# TAKEMINAKATA.net
KiCad netlist of a schematic drawn in EasyEDA
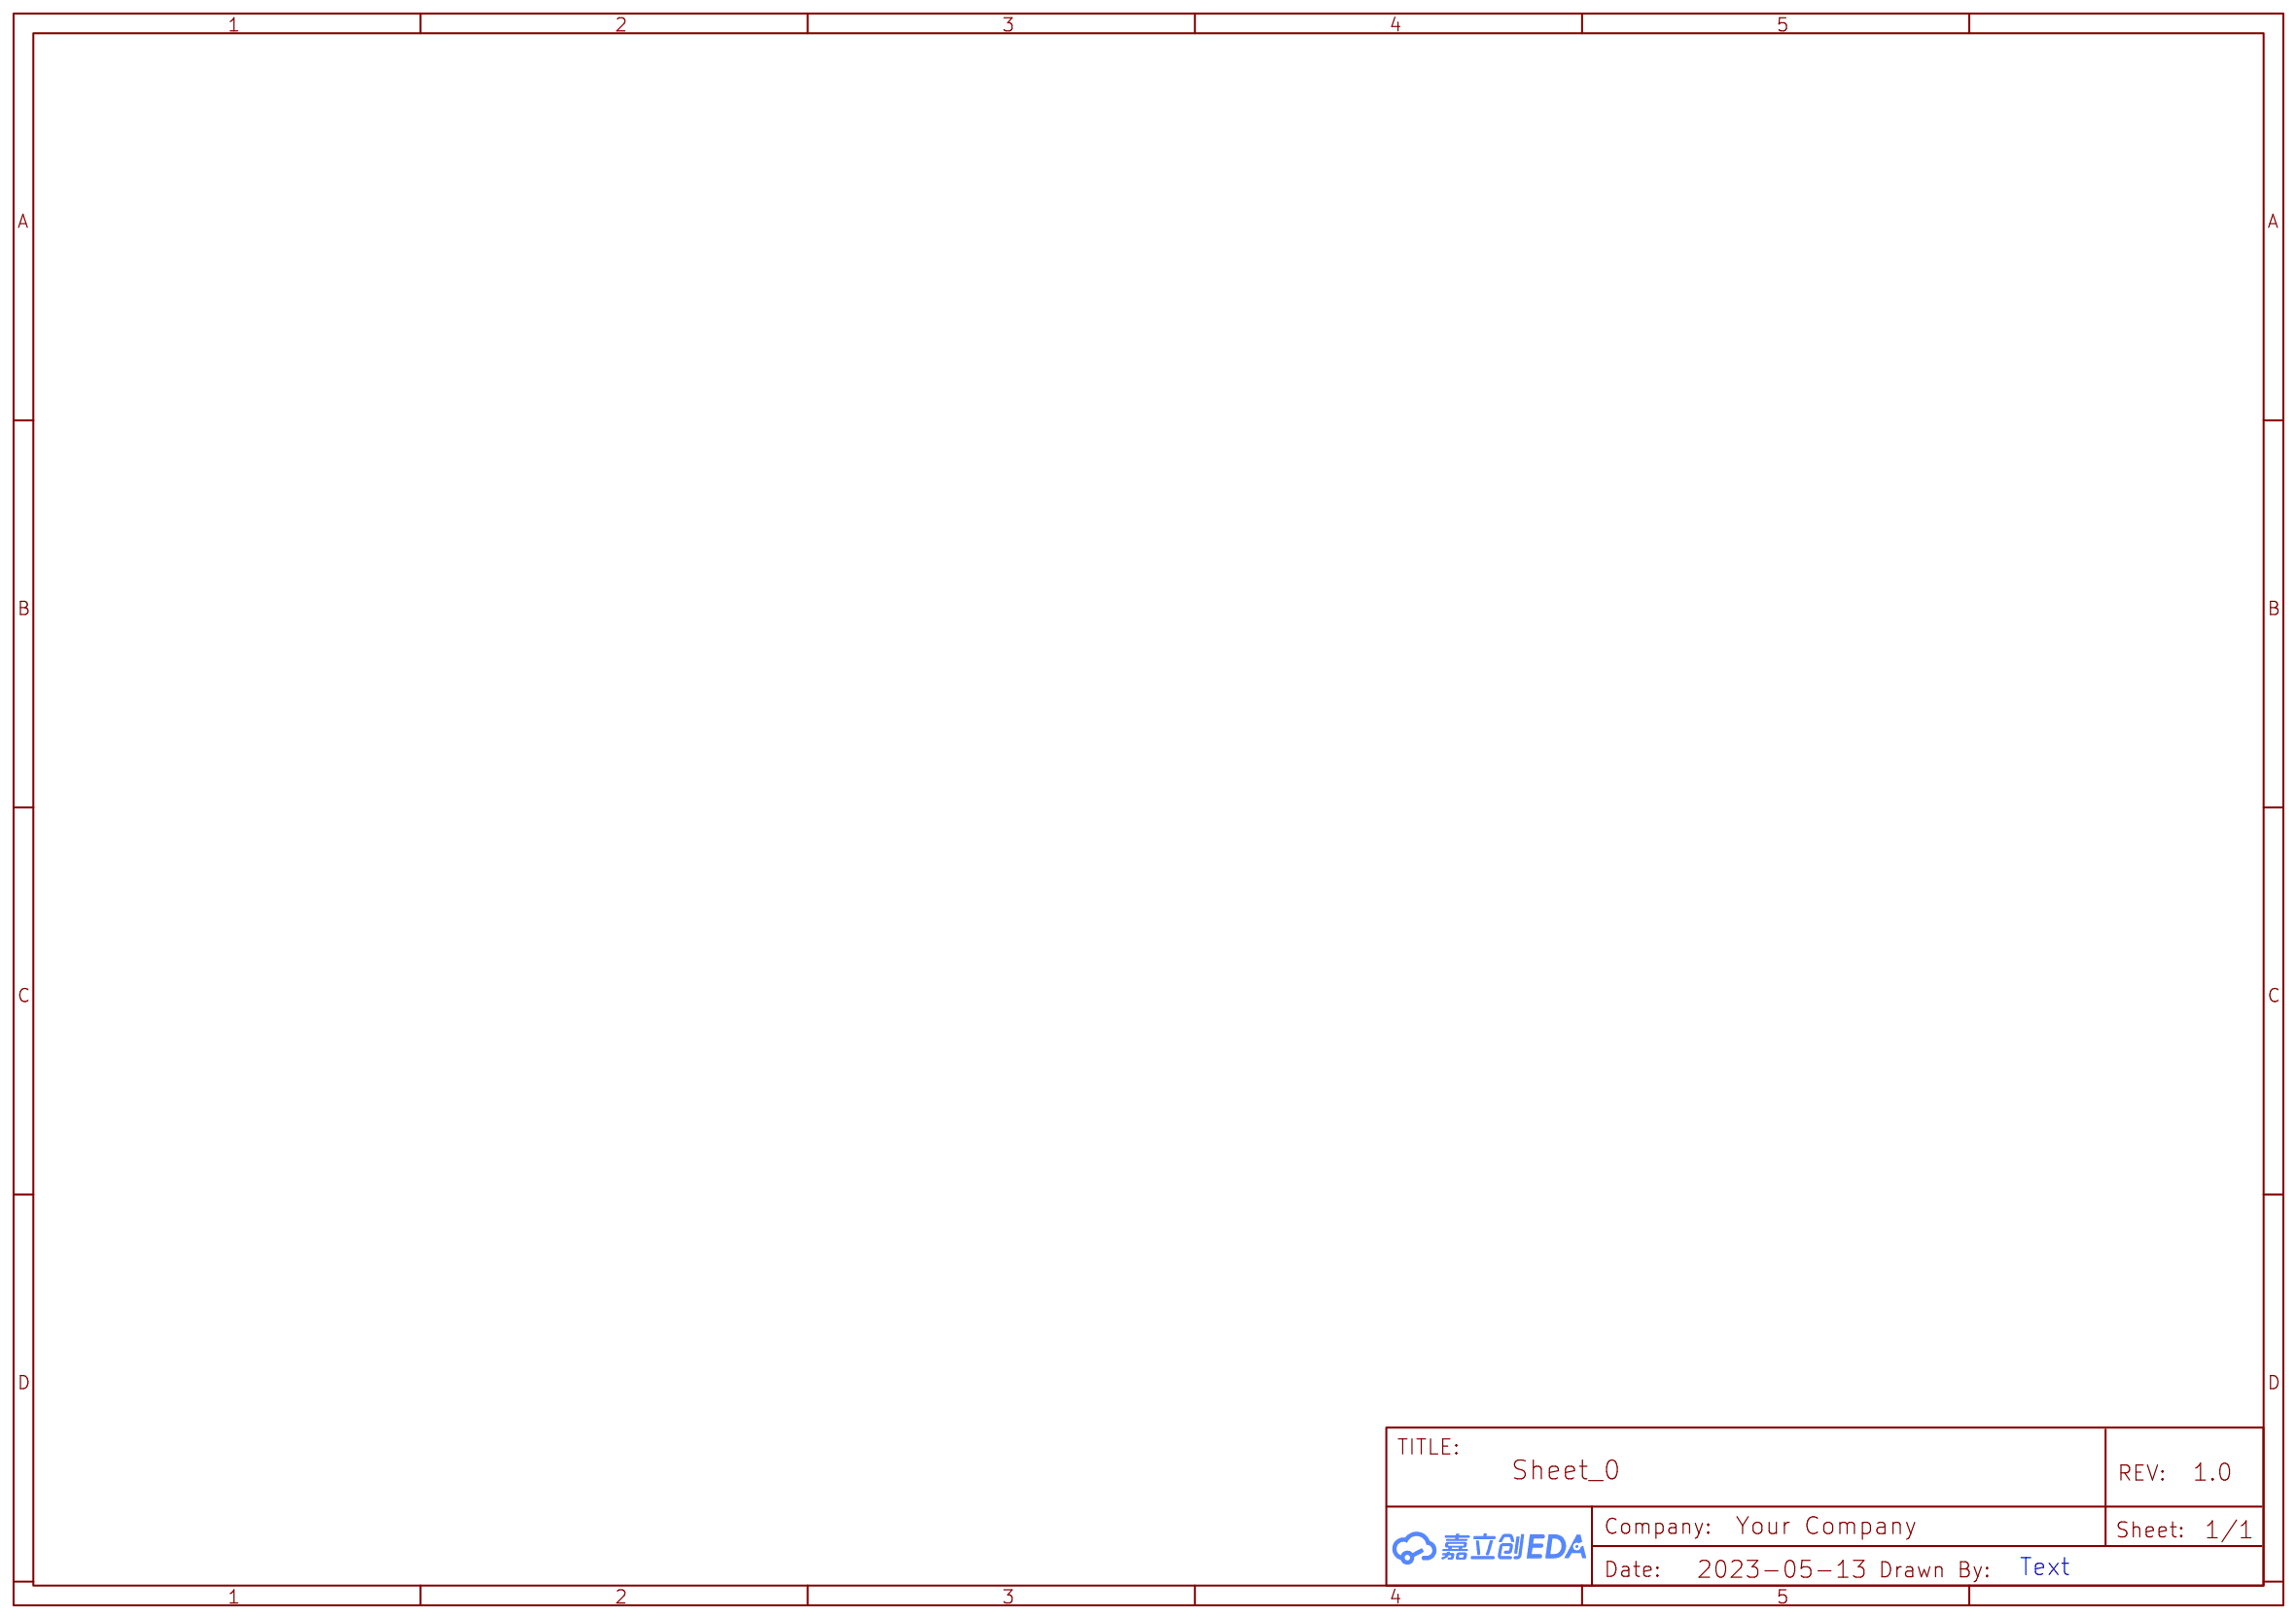
[diagram p0: Sheet_1]
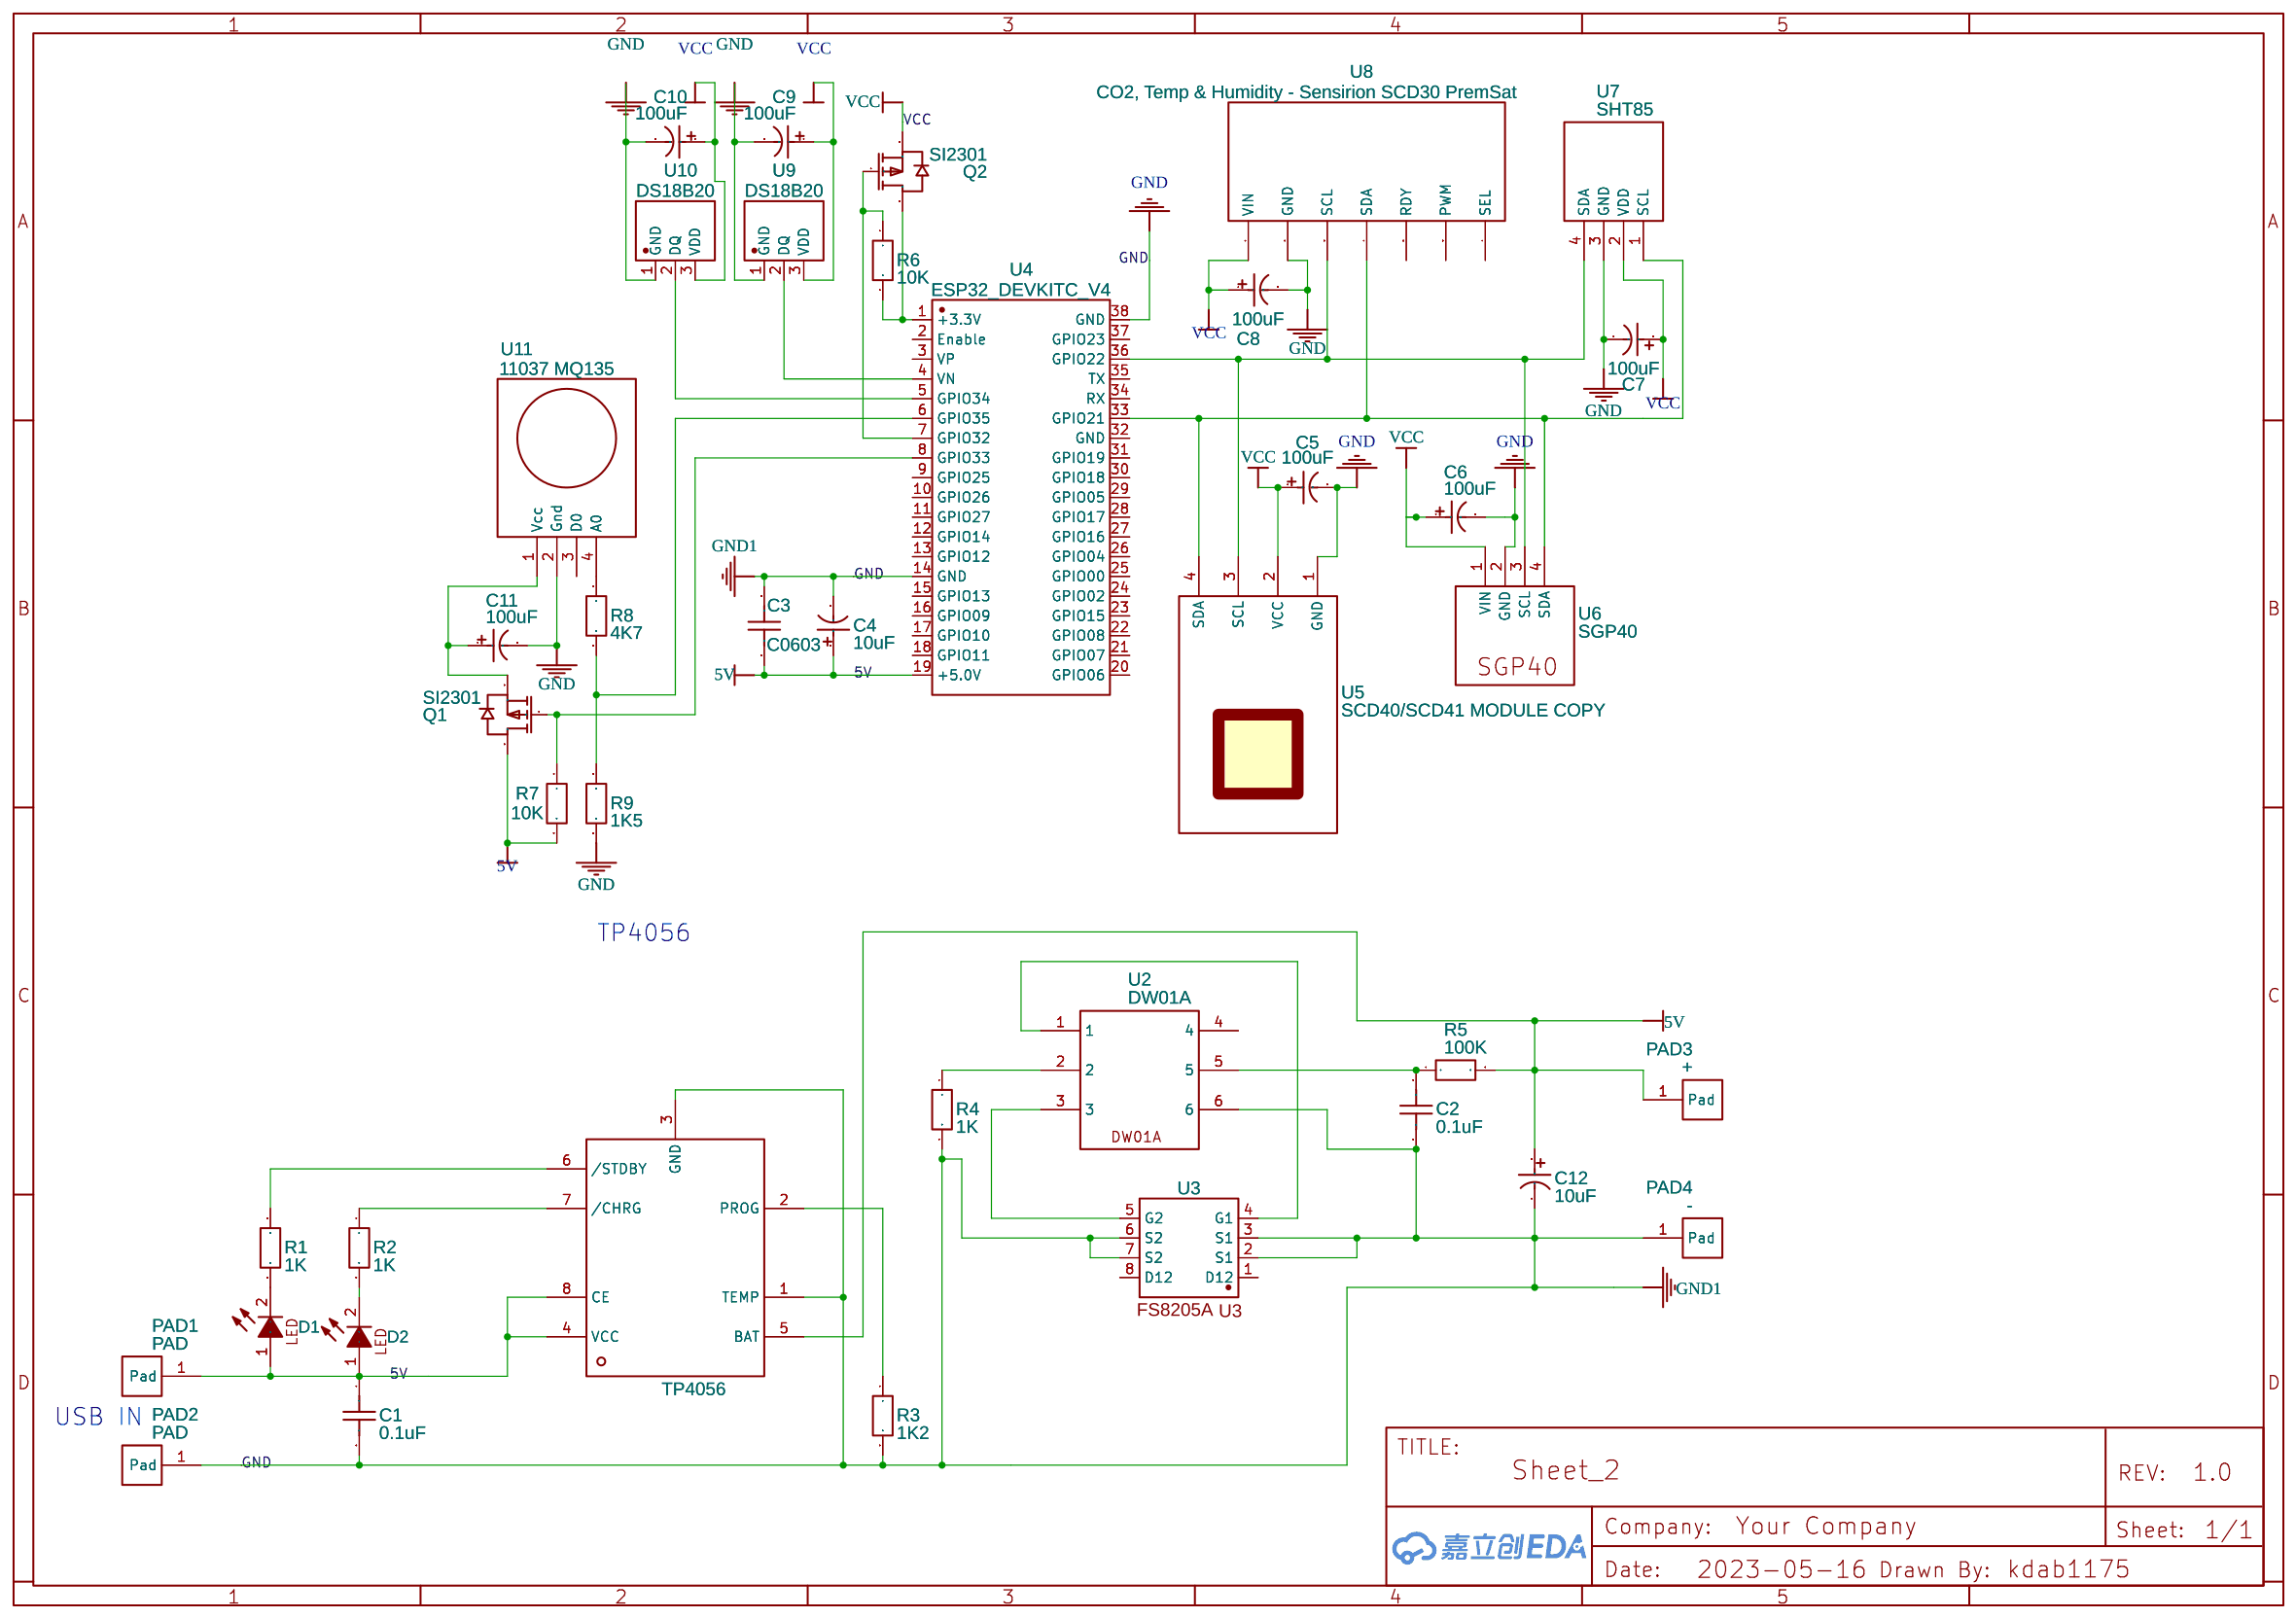
[diagram p1: Sheet_2]

(export (version "E")
  (design (tool "Eeschema 10.0.6"))
  (components
    (comp (ref "C1") (value "0.1uF") (libsource (lib "") (part "C_0603_US")))
    (comp (ref "C2") (value "0.1uF") (libsource (lib "") (part "C_0603_US")))
    (comp (ref "C3")
      (value "C0603")
      (fields (field (name "BOM_Manufacturer Part") "10uF") (field (name "BOM_Supplier Part") "C15415"))
      (libsource (lib "") (part "C 0603"))
    )
    (comp (ref "C4")
      (value "10uF")
      (fields
        (field (name "BOM_Manufacturer Part") "KF106M016B05RR0VH2FP0")
        (field (name "BOM_Supplier Part") "C43798")
      )
      (libsource (lib "") (part "10uF 16V 3*5_1"))
    )
    (comp (ref "C5")
      (value "100uF")
      (fields
        (field (name "BOM_Manufacturer Part") "100uF 35V 6.3*11")
        (field (name "BOM_Supplier Part") "C45076")
      )
      (libsource (lib "") (part "100uF 35V 6.3*11_C45076_1"))
    )
    (comp (ref "C6")
      (value "100uF")
      (fields
        (field (name "BOM_Manufacturer Part") "100uF 35V 6.3*11")
        (field (name "BOM_Supplier Part") "C45076")
      )
      (libsource (lib "") (part "100uF 35V 6.3*11_C45076_1"))
    )
    (comp (ref "C7")
      (value "100uF")
      (fields
        (field (name "BOM_Manufacturer Part") "100uF 35V 6.3*11")
        (field (name "BOM_Supplier Part") "C45076")
      )
      (libsource (lib "") (part "100uF 35V 6.3*11_C45076_2"))
    )
    (comp (ref "C8")
      (value "100uF")
      (fields
        (field (name "BOM_Manufacturer Part") "100uF 35V 6.3*11")
        (field (name "BOM_Supplier Part") "C45076")
      )
      (libsource (lib "") (part "100uF 35V 6.3*11_C45076_1"))
    )
    (comp (ref "C9")
      (value "100uF")
      (fields
        (field (name "BOM_Manufacturer Part") "100uF 35V 6.3*11")
        (field (name "BOM_Supplier Part") "C45076")
      )
      (libsource (lib "") (part "100uF 35V 6.3*11_C45076"))
    )
    (comp (ref "C10")
      (value "100uF")
      (fields
        (field (name "BOM_Manufacturer Part") "100uF 35V 6.3*11")
        (field (name "BOM_Supplier Part") "C45076")
      )
      (libsource (lib "") (part "100uF 35V 6.3*11_C45076"))
    )
    (comp (ref "C11")
      (value "100uF")
      (fields
        (field (name "BOM_Manufacturer Part") "100uF 35V 6.3*11")
        (field (name "BOM_Supplier Part") "C45076")
      )
      (libsource (lib "") (part "100uF 35V 6.3*11_C45076_1"))
    )
    (comp (ref "C12")
      (value "10uF")
      (fields
        (field (name "BOM_Manufacturer Part") "KF106M016B05RR0VH2FP0")
        (field (name "BOM_Supplier Part") "C43798")
      )
      (libsource (lib "") (part "10uF 16V 3*5"))
    )
    (comp (ref "D1")
      (value "LED")
      (fields (field (name "BOM_Manufacturer Part") "5600") (field (name "BOM_Supplier Part") "L20325-ND"))
      (libsource (lib "") (part "LED"))
    )
    (comp (ref "D2")
      (value "LED COPY")
      (fields (field (name "BOM_Manufacturer Part") "5600") (field (name "BOM_Supplier Part") "L20325-ND"))
      (libsource (lib "") (part "LED"))
    )
    (comp (ref "PAD1") (value "PAD") (libsource (lib "") (part "PAD COPY COPY_1")))
    (comp (ref "PAD2") (value "PAD") (libsource (lib "") (part "PAD COPY COPY_1")))
    (comp (ref "PAD3") (value "+") (libsource (lib "") (part "PAD COPY COPY")))
    (comp (ref "PAD4") (value "-") (libsource (lib "") (part "PAD COPY COPY")))
    (comp (ref "Q1")
      (value "SI2301")
      (fields (field (name "BOM_Manufacturer Part") "SI2301DS") (field (name "BOM_Supplier Part") "C2841444"))
      (libsource (lib "") (part "SI2301DS_TH"))
    )
    (comp (ref "Q2")
      (value "SI2301")
      (fields (field (name "BOM_Manufacturer Part") "SI2301DS") (field (name "BOM_Supplier Part") "C2841444"))
      (libsource (lib "") (part "SI2301DS_TH_1"))
    )
    (comp (ref "R1") (value "1K") (libsource (lib "") (part "R_0603_EU_1")))
    (comp (ref "R2") (value "1K") (libsource (lib "") (part "R_0603_EU_1")))
    (comp (ref "R3") (value "1K2") (libsource (lib "") (part "R_0603_EU_1")))
    (comp (ref "R4") (value "1K") (libsource (lib "") (part "R_0603_EU_1")))
    (comp (ref "R5") (value "100K") (libsource (lib "") (part "R_0603_EU")))
    (comp (ref "R6") (value "10K") (libsource (lib "") (part "R_0603_EU_1")))
    (comp (ref "R7") (value "10K") (libsource (lib "") (part "R_0603_EU_1")))
    (comp (ref "R8") (value "4K7") (libsource (lib "") (part "R_0603_EU_1")))
    (comp (ref "R9") (value "1K5") (libsource (lib "") (part "R_0603_EU_1")))
    (comp (ref "U1")
      (value "TP4056")
      (fields
        (field (name "BOM_Manufacturer Part") "TP4056-42-SOP8-PP")
        (field (name "BOM_Supplier Part") "3656")
      )
      (libsource (lib "") (part "TP4056"))
    )
    (comp (ref "U2") (value "DW01A") (libsource (lib "") (part "DW01A")))
    (comp (ref "U3") (value "FS8205A MODIF") (libsource (lib "") (part "FS8205A MODIF")))
    (comp (ref "U4")
      (value "ESP32_DEVKITC_V4")
      (fields (field (name "BOM_Supplier Part") "A5130"))
      (libsource (lib "") (part "ESP32_DEVKITC_V4"))
    )
    (comp (ref "U5") (value "SCD40/SCD41 MODULE COPY") (libsource (lib "") (part "SCD40/SCD41 MODULE COPY")))
    (comp (ref "U6") (value "SGP40") (libsource (lib "") (part "SGP40")))
    (comp (ref "U7")
      (value "SHT85")
      (fields (field (name "BOM_Supplier Part") "403-SHT85"))
      (libsource (lib "") (part "SHT85"))
    )
    (comp (ref "U8")
      (value "CO2, Temp & Humidity - Sensirion SCD30 PremSat")
      (fields
        (field (name "BOM_Manufacturer Part") "SCD30")
        (field (name "BOM_Supplier Part") "1649-1098-ND")
      )
      (libsource (lib "") (part "CO2, Temp & Humidity - Sensirion SCD30 PremSat"))
    )
    (comp (ref "U9")
      (value "DS18B20")
      (fields (field (name "BOM_Supplier Part") "C5379069"))
      (libsource (lib "") (part "DS18B20_C5379069"))
    )
    (comp (ref "U10")
      (value "DS18B20")
      (fields (field (name "BOM_Supplier Part") "C5379069"))
      (libsource (lib "") (part "DS18B20_C5379069"))
    )
    (comp (ref "U11") (value "11037 MQ135") (libsource (lib "") (part "11037 MQ135")))
  )
  (nets
    (net (code "1") (name "5V") (class "Default")
      (node (ref "C1") (pin "1") (pinfunction "1_1") (pintype "unspecified"))
      (node (ref "C12") (pin "1") (pinfunction "1_1") (pintype "input"))
      (node (ref "C3") (pin "1") (pinfunction "1_1") (pintype "unspecified"))
      (node (ref "C4") (pin "1") (pinfunction "1_1") (pintype "input"))
      (node (ref "D1") (pin "1") (pinfunction "A_1") (pintype "unspecified"))
      (node (ref "D2") (pin "1") (pinfunction "A_1") (pintype "unspecified"))
      (node (ref "PAD1") (pin "1") (pinfunction "Pad_1") (pintype "unspecified"))
      (node (ref "PAD3") (pin "1") (pinfunction "Pad_1") (pintype "unspecified"))
      (node (ref "Q1") (pin "3") (pinfunction "D_3") (pintype "unspecified"))
      (node (ref "R5") (pin "2") (pinfunction "2_2") (pintype "unspecified"))
      (node (ref "R7") (pin "2") (pinfunction "2_2") (pintype "unspecified"))
      (node (ref "U1") (pin "4") (pinfunction "VCC_4") (pintype "unspecified"))
      (node (ref "U1") (pin "5") (pinfunction "BAT_5") (pintype "unspecified"))
      (node (ref "U1") (pin "8") (pinfunction "CE_8") (pintype "unspecified"))
      (node (ref "U4") (pin "19") (pinfunction "+5.0V_19") (pintype "unspecified"))
    )
    (net (code "2") (name "GND") (class "Default")
      (node (ref "C1") (pin "2") (pinfunction "2_2") (pintype "unspecified"))
      (node (ref "C10") (pin "2") (pinfunction "2_2") (pintype "input"))
      (node (ref "C11") (pin "2") (pinfunction "2_2") (pintype "input"))
      (node (ref "C12") (pin "2") (pinfunction "2_2") (pintype "input"))
      (node (ref "C2") (pin "2") (pinfunction "2_2") (pintype "unspecified"))
      (node (ref "C3") (pin "2") (pinfunction "2_2") (pintype "unspecified"))
      (node (ref "C4") (pin "2") (pinfunction "2_2") (pintype "input"))
      (node (ref "C5") (pin "2") (pinfunction "2_2") (pintype "input"))
      (node (ref "C6") (pin "2") (pinfunction "2_2") (pintype "input"))
      (node (ref "C7") (pin "2") (pinfunction "2_2") (pintype "input"))
      (node (ref "C8") (pin "2") (pinfunction "2_2") (pintype "input"))
      (node (ref "C9") (pin "2") (pinfunction "2_2") (pintype "input"))
      (node (ref "PAD2") (pin "1") (pinfunction "Pad_1") (pintype "unspecified"))
      (node (ref "PAD4") (pin "1") (pinfunction "Pad_1") (pintype "unspecified"))
      (node (ref "R3") (pin "2") (pinfunction "2_2") (pintype "unspecified"))
      (node (ref "R4") (pin "2") (pinfunction "2_2") (pintype "unspecified"))
      (node (ref "R9") (pin "2") (pinfunction "2_2") (pintype "unspecified"))
      (node (ref "U1") (pin "1") (pinfunction "TEMP_1") (pintype "unspecified"))
      (node (ref "U1") (pin "3") (pinfunction "GND_3") (pintype "unspecified"))
      (node (ref "U10") (pin "1") (pinfunction "GND_1") (pintype "unspecified"))
      (node (ref "U11") (pin "2") (pinfunction "Gnd_2") (pintype "unspecified"))
      (node (ref "U2") (pin "6") (pinfunction "6_6") (pintype "unspecified"))
      (node (ref "U3") (pin "2") (pinfunction "S1_2") (pintype "unspecified"))
      (node (ref "U3") (pin "3") (pinfunction "S1_3") (pintype "unspecified"))
      (node (ref "U3") (pin "6") (pinfunction "S2_6") (pintype "unspecified"))
      (node (ref "U3") (pin "7") (pinfunction "S2_7") (pintype "unspecified"))
      (node (ref "U4") (pin "14") (pinfunction "GND_14") (pintype "unspecified"))
      (node (ref "U4") (pin "38") (pinfunction "GND_38") (pintype "unspecified"))
      (node (ref "U5") (pin "1") (pinfunction "GND_1") (pintype "unspecified"))
      (node (ref "U6") (pin "2") (pinfunction "GND_2") (pintype "unspecified"))
      (node (ref "U7") (pin "3") (pinfunction "GND_3") (pintype "unspecified"))
      (node (ref "U8") (pin "2") (pinfunction "GND_2") (pintype "unspecified"))
      (node (ref "U9") (pin "1") (pinfunction "GND_1") (pintype "unspecified"))
    )
    (net (code "3") (name "Net-(C2-Pad1)") (class "Default")
      (node (ref "C2") (pin "1") (pinfunction "1_1") (pintype "unspecified"))
      (node (ref "R5") (pin "1") (pinfunction "1_1") (pintype "unspecified"))
      (node (ref "U2") (pin "5") (pinfunction "5_5") (pintype "unspecified"))
    )
    (net (code "4") (name "Net-(D1-K)") (class "Default")
      (node (ref "D1") (pin "2") (pinfunction "K_2") (pintype "unspecified"))
      (node (ref "R1") (pin "2") (pinfunction "2_2") (pintype "unspecified"))
    )
    (net (code "5") (name "Net-(D2-K)") (class "Default")
      (node (ref "D2") (pin "2") (pinfunction "K_2") (pintype "unspecified"))
      (node (ref "R2") (pin "2") (pinfunction "2_2") (pintype "unspecified"))
    )
    (net (code "6") (name "Net-(Q1-G)") (class "Default")
      (node (ref "Q1") (pin "1") (pinfunction "G_1") (pintype "unspecified"))
      (node (ref "R7") (pin "1") (pinfunction "1_1") (pintype "unspecified"))
      (node (ref "U4") (pin "8") (pinfunction "GPIO33_8") (pintype "unspecified"))
    )
    (net (code "7") (name "Net-(Q1-S)") (class "Default")
      (node (ref "C11") (pin "1") (pinfunction "1_1") (pintype "input"))
      (node (ref "Q1") (pin "2") (pinfunction "S_2") (pintype "unspecified"))
      (node (ref "U11") (pin "1") (pinfunction "Vcc_1") (pintype "unspecified"))
    )
    (net (code "8") (name "Net-(Q2-D)") (class "Default")
      (node (ref "Q2") (pin "3") (pinfunction "D_3") (pintype "unspecified"))
      (node (ref "R6") (pin "2") (pinfunction "2_2") (pintype "unspecified"))
      (node (ref "U4") (pin "1") (pinfunction "+3.3V_1") (pintype "unspecified"))
    )
    (net (code "9") (name "Net-(Q2-G)") (class "Default")
      (node (ref "Q2") (pin "1") (pinfunction "G_1") (pintype "unspecified"))
      (node (ref "R6") (pin "1") (pinfunction "1_1") (pintype "unspecified"))
      (node (ref "U4") (pin "7") (pinfunction "GPIO32_7") (pintype "unspecified"))
    )
    (net (code "10") (name "Net-(R4-Pad1)") (class "Default")
      (node (ref "R4") (pin "1") (pinfunction "1_1") (pintype "unspecified"))
      (node (ref "U2") (pin "2") (pinfunction "2_2") (pintype "unspecified"))
    )
    (net (code "11") (name "Net-(U1-PROG)") (class "Default")
      (node (ref "R3") (pin "1") (pinfunction "1_1") (pintype "unspecified"))
      (node (ref "U1") (pin "2") (pinfunction "PROG_2") (pintype "unspecified"))
    )
    (net (code "12") (name "Net-(U1-{slash}CHRG)") (class "Default")
      (node (ref "R2") (pin "1") (pinfunction "1_1") (pintype "unspecified"))
      (node (ref "U1") (pin "7") (pinfunction "/CHRG_7") (pintype "unspecified"))
    )
    (net (code "13") (name "Net-(U1-{slash}STDBY)") (class "Default")
      (node (ref "R1") (pin "1") (pinfunction "1_1") (pintype "unspecified"))
      (node (ref "U1") (pin "6") (pinfunction "/STDBY_6") (pintype "unspecified"))
    )
    (net (code "14") (name "Net-(U3-G1)") (class "Default")
      (node (ref "U2") (pin "1") (pinfunction "1_1") (pintype "unspecified"))
      (node (ref "U3") (pin "4") (pinfunction "G1_4") (pintype "unspecified"))
    )
    (net (code "15") (name "Net-(U3-G2)") (class "Default")
      (node (ref "U2") (pin "3") (pinfunction "3_3") (pintype "unspecified"))
      (node (ref "U3") (pin "5") (pinfunction "G2_5") (pintype "unspecified"))
    )
    (net (code "16") (name "Net-(U4-GPIO21)") (class "Default")
      (node (ref "U4") (pin "33") (pinfunction "GPIO21_33") (pintype "unspecified"))
      (node (ref "U5") (pin "4") (pinfunction "SDA_4") (pintype "unspecified"))
      (node (ref "U6") (pin "4") (pinfunction "SDA_4") (pintype "unspecified"))
      (node (ref "U7") (pin "1") (pinfunction "SCL_1") (pintype "unspecified"))
      (node (ref "U8") (pin "4") (pinfunction "SDA_4") (pintype "unspecified"))
    )
    (net (code "17") (name "Net-(U4-GPIO22)") (class "Default")
      (node (ref "U4") (pin "36") (pinfunction "GPIO22_36") (pintype "unspecified"))
      (node (ref "U5") (pin "3") (pinfunction "SCL_3") (pintype "unspecified"))
      (node (ref "U6") (pin "3") (pinfunction "SCL_3") (pintype "unspecified"))
      (node (ref "U7") (pin "4") (pinfunction "SDA_4") (pintype "unspecified"))
      (node (ref "U8") (pin "3") (pinfunction "SCL_3") (pintype "unspecified"))
    )
    (net (code "18") (name "Net-(U4-GPIO35)") (class "Default")
      (node (ref "R8") (pin "2") (pinfunction "2_2") (pintype "unspecified"))
      (node (ref "R9") (pin "1") (pinfunction "1_1") (pintype "unspecified"))
      (node (ref "U4") (pin "6") (pinfunction "GPIO35_6") (pintype "unspecified"))
    )
    (net (code "19") (name "Net-(U4-VN)") (class "Default")
      (node (ref "U4") (pin "4") (pinfunction "VN_4") (pintype "unspecified"))
      (node (ref "U9") (pin "2") (pinfunction "DQ_2") (pintype "unspecified"))
    )
    (net (code "20") (name "Net-(U10-DQ)") (class "Default")
      (node (ref "U10") (pin "2") (pinfunction "DQ_2") (pintype "unspecified"))
      (node (ref "U4") (pin "5") (pinfunction "GPIO34_5") (pintype "unspecified"))
    )
    (net (code "21") (name "Net-(U11-A0)") (class "Default")
      (node (ref "R8") (pin "1") (pinfunction "1_1") (pintype "unspecified"))
      (node (ref "U11") (pin "4") (pinfunction "A0_4") (pintype "unspecified"))
    )
    (net (code "22") (name "VCC") (class "Default")
      (node (ref "C10") (pin "1") (pinfunction "1_1") (pintype "input"))
      (node (ref "C5") (pin "1") (pinfunction "1_1") (pintype "input"))
      (node (ref "C6") (pin "1") (pinfunction "1_1") (pintype "input"))
      (node (ref "C7") (pin "1") (pinfunction "1_1") (pintype "input"))
      (node (ref "C8") (pin "1") (pinfunction "1_1") (pintype "input"))
      (node (ref "C9") (pin "1") (pinfunction "1_1") (pintype "input"))
      (node (ref "Q2") (pin "2") (pinfunction "S_2") (pintype "unspecified"))
      (node (ref "U10") (pin "3") (pinfunction "VDD_3") (pintype "unspecified"))
      (node (ref "U5") (pin "2") (pinfunction "VCC_2") (pintype "unspecified"))
      (node (ref "U6") (pin "1") (pinfunction "VIN_1") (pintype "unspecified"))
      (node (ref "U7") (pin "2") (pinfunction "VDD_2") (pintype "unspecified"))
      (node (ref "U8") (pin "1") (pinfunction "VIN_1") (pintype "unspecified"))
      (node (ref "U9") (pin "3") (pinfunction "VDD_3") (pintype "unspecified"))
    )
    (net (code "23") (name "unconnected-(U2-Pad4)") (class "Default")
      (node (ref "U2") (pin "4") (pinfunction "4_4") (pintype "unspecified"))
    )
    (net (code "24") (name "unconnected-(U3-D12-Pad1)") (class "Default")
      (node (ref "U3") (pin "1") (pinfunction "D12_1") (pintype "unspecified"))
    )
    (net (code "25") (name "unconnected-(U3-D12-Pad8)") (class "Default")
      (node (ref "U3") (pin "8") (pinfunction "D12_8") (pintype "unspecified"))
    )
    (net (code "26") (name "unconnected-(U4-Enable-Pad2)") (class "Default")
      (node (ref "U4") (pin "2") (pinfunction "Enable_2") (pintype "unspecified"))
    )
    (net (code "27") (name "unconnected-(U4-GND-Pad32)") (class "Default")
      (node (ref "U4") (pin "32") (pinfunction "GND_32") (pintype "unspecified"))
    )
    (net (code "28") (name "unconnected-(U4-GPIO00-Pad25)") (class "Default")
      (node (ref "U4") (pin "25") (pinfunction "GPIO00_25") (pintype "unspecified"))
    )
    (net (code "29") (name "unconnected-(U4-GPIO02-Pad24)") (class "Default")
      (node (ref "U4") (pin "24") (pinfunction "GPIO02_24") (pintype "unspecified"))
    )
    (net (code "30") (name "unconnected-(U4-GPIO04-Pad26)") (class "Default")
      (node (ref "U4") (pin "26") (pinfunction "GPIO04_26") (pintype "unspecified"))
    )
    (net (code "31") (name "unconnected-(U4-GPIO05-Pad29)") (class "Default")
      (node (ref "U4") (pin "29") (pinfunction "GPIO05_29") (pintype "unspecified"))
    )
    (net (code "32") (name "unconnected-(U4-GPIO06-Pad20)") (class "Default")
      (node (ref "U4") (pin "20") (pinfunction "GPIO06_20") (pintype "unspecified"))
    )
    (net (code "33") (name "unconnected-(U4-GPIO07-Pad21)") (class "Default")
      (node (ref "U4") (pin "21") (pinfunction "GPIO07_21") (pintype "unspecified"))
    )
    (net (code "34") (name "unconnected-(U4-GPIO08-Pad22)") (class "Default")
      (node (ref "U4") (pin "22") (pinfunction "GPIO08_22") (pintype "unspecified"))
    )
    (net (code "35") (name "unconnected-(U4-GPIO09-Pad16)") (class "Default")
      (node (ref "U4") (pin "16") (pinfunction "GPIO09_16") (pintype "unspecified"))
    )
    (net (code "36") (name "unconnected-(U4-GPIO10-Pad17)") (class "Default")
      (node (ref "U4") (pin "17") (pinfunction "GPIO10_17") (pintype "unspecified"))
    )
    (net (code "37") (name "unconnected-(U4-GPIO11-Pad18)") (class "Default")
      (node (ref "U4") (pin "18") (pinfunction "GPIO11_18") (pintype "unspecified"))
    )
    (net (code "38") (name "unconnected-(U4-GPIO12-Pad13)") (class "Default")
      (node (ref "U4") (pin "13") (pinfunction "GPIO12_13") (pintype "unspecified"))
    )
    (net (code "39") (name "unconnected-(U4-GPIO13-Pad15)") (class "Default")
      (node (ref "U4") (pin "15") (pinfunction "GPIO13_15") (pintype "unspecified"))
    )
    (net (code "40") (name "unconnected-(U4-GPIO14-Pad12)") (class "Default")
      (node (ref "U4") (pin "12") (pinfunction "GPIO14_12") (pintype "unspecified"))
    )
    (net (code "41") (name "unconnected-(U4-GPIO15-Pad23)") (class "Default")
      (node (ref "U4") (pin "23") (pinfunction "GPIO15_23") (pintype "unspecified"))
    )
    (net (code "42") (name "unconnected-(U4-GPIO16-Pad27)") (class "Default")
      (node (ref "U4") (pin "27") (pinfunction "GPIO16_27") (pintype "unspecified"))
    )
    (net (code "43") (name "unconnected-(U4-GPIO17-Pad28)") (class "Default")
      (node (ref "U4") (pin "28") (pinfunction "GPIO17_28") (pintype "unspecified"))
    )
    (net (code "44") (name "unconnected-(U4-GPIO18-Pad30)") (class "Default")
      (node (ref "U4") (pin "30") (pinfunction "GPIO18_30") (pintype "unspecified"))
    )
    (net (code "45") (name "unconnected-(U4-GPIO19-Pad31)") (class "Default")
      (node (ref "U4") (pin "31") (pinfunction "GPIO19_31") (pintype "unspecified"))
    )
    (net (code "46") (name "unconnected-(U4-GPIO23-Pad37)") (class "Default")
      (node (ref "U4") (pin "37") (pinfunction "GPIO23_37") (pintype "unspecified"))
    )
    (net (code "47") (name "unconnected-(U4-GPIO25-Pad9)") (class "Default")
      (node (ref "U4") (pin "9") (pinfunction "GPIO25_9") (pintype "unspecified"))
    )
    (net (code "48") (name "unconnected-(U4-GPIO26-Pad10)") (class "Default")
      (node (ref "U4") (pin "10") (pinfunction "GPIO26_10") (pintype "unspecified"))
    )
    (net (code "49") (name "unconnected-(U4-GPIO27-Pad11)") (class "Default")
      (node (ref "U4") (pin "11") (pinfunction "GPIO27_11") (pintype "unspecified"))
    )
    (net (code "50") (name "unconnected-(U4-RX-Pad34)") (class "Default")
      (node (ref "U4") (pin "34") (pinfunction "RX_34") (pintype "unspecified"))
    )
    (net (code "51") (name "unconnected-(U4-TX-Pad35)") (class "Default")
      (node (ref "U4") (pin "35") (pinfunction "TX_35") (pintype "unspecified"))
    )
    (net (code "52") (name "unconnected-(U4-VP-Pad3)") (class "Default")
      (node (ref "U4") (pin "3") (pinfunction "VP_3") (pintype "unspecified"))
    )
    (net (code "53") (name "unconnected-(U8-PWM-Pad6)") (class "Default")
      (node (ref "U8") (pin "6") (pinfunction "PWM_6") (pintype "unspecified"))
    )
    (net (code "54") (name "unconnected-(U8-RDY-Pad5)") (class "Default")
      (node (ref "U8") (pin "5") (pinfunction "RDY_5") (pintype "unspecified"))
    )
    (net (code "55") (name "unconnected-(U8-SEL-Pad7)") (class "Default")
      (node (ref "U8") (pin "7") (pinfunction "SEL_7") (pintype "unspecified"))
    )
    (net (code "56") (name "unconnected-(U11-D0-Pad3)") (class "Default")
      (node (ref "U11") (pin "3") (pinfunction "D0_3") (pintype "unspecified"))
    )
  )
)
